# white_noise.net
KiCad netlist of a schematic drawn in Altium Designer
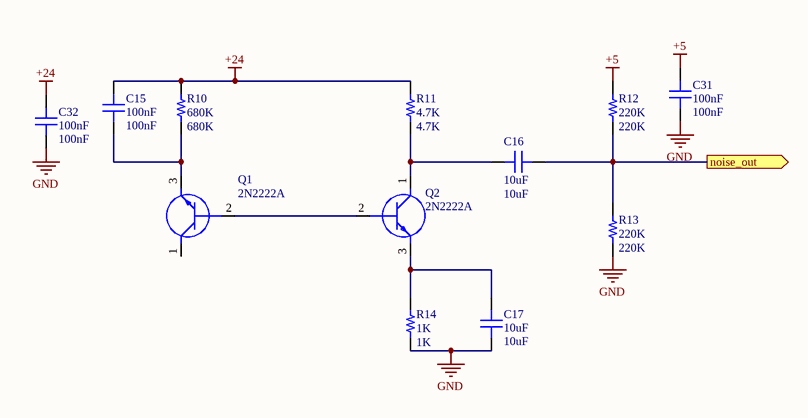
[diagram p0: white_noise.SchDoc]

(export (version "E")
  (design (tool "Eeschema 10.0.6"))
  (components
    (comp (ref "C15")
      (value "100nF")
      (footprint "cap805")
      (description "CAP SMD 0805")
      (fields (field (name "PART NUMBER") "C0805X106K9RAC7800") (field (name "ALTIUM_VALUE") "100nF"))
      (libsource (lib "lamp control-ver2") (part "Capacitor"))
    )
    (comp (ref "C16")
      (value "10uF")
      (footprint "cap805")
      (description "CAP SMD 0805")
      (fields (field (name "PART NUMBER") "C0805X106K9RAC7800") (field (name "ALTIUM_VALUE") "10uF"))
      (libsource (lib "lamp control-ver2") (part "Capacitor"))
    )
    (comp (ref "C17")
      (value "10uF")
      (footprint "cap805")
      (description "CAP SMD 0805")
      (fields (field (name "PART NUMBER") "C0805X106K9RAC7800") (field (name "ALTIUM_VALUE") "10uF"))
      (libsource (lib "lamp control-ver2") (part "Capacitor"))
    )
    (comp (ref "C31")
      (value "100nF")
      (footprint "cap805")
      (description "CAP SMD 0805")
      (fields (field (name "PART NUMBER") "C0805X106K9RAC7800") (field (name "ALTIUM_VALUE") "100nF"))
      (libsource (lib "lamp control-ver2") (part "Capacitor"))
    )
    (comp (ref "C32")
      (value "100nF")
      (footprint "cap805")
      (description "CAP SMD 0805")
      (fields (field (name "PART NUMBER") "C0805X106K9RAC7800") (field (name "ALTIUM_VALUE") "100nF"))
      (libsource (lib "lamp control-ver2") (part "Capacitor"))
    )
    (comp (ref "Q1")
      (value "2N2222A")
      (footprint "soT95p280x130-3n")
      (description "Transistor BJT NPN SMD")
      (libsource (lib "*") (part "2N2222A"))
    )
    (comp (ref "Q2")
      (value "2N2222A")
      (footprint "soT95p280x130-3n")
      (description "Transistor BJT NPN SMD")
      (libsource (lib "*") (part "2N2222A"))
    )
    (comp (ref "R10")
      (value "680K")
      (footprint "0603R")
      (description "RES SMD 0603")
      (fields (field (name "PART NUMBER") "RCS0805100KFKEA") (field (name "ALTIUM_VALUE") "680K"))
      (libsource (lib "lamp control-ver2") (part "Resistor"))
    )
    (comp (ref "R11")
      (value "4.7K")
      (footprint "0603R")
      (description "RES SMD 0603")
      (fields (field (name "PART NUMBER") "RCS0805100KFKEA") (field (name "ALTIUM_VALUE") "4.7K"))
      (libsource (lib "lamp control-ver2") (part "Resistor"))
    )
    (comp (ref "R12")
      (value "220K")
      (footprint "0603R")
      (description "RES SMD 0603")
      (fields (field (name "PART NUMBER") "RCS0805100KFKEA") (field (name "ALTIUM_VALUE") "220K"))
      (libsource (lib "lamp control-ver2") (part "Resistor"))
    )
    (comp (ref "R13")
      (value "220K")
      (footprint "0603R")
      (description "RES SMD 0603")
      (fields (field (name "PART NUMBER") "RCS0805100KFKEA") (field (name "ALTIUM_VALUE") "220K"))
      (libsource (lib "lamp control-ver2") (part "Resistor"))
    )
    (comp (ref "R14")
      (value "1K")
      (footprint "0603R")
      (description "RES SMD 0603")
      (fields (field (name "PART NUMBER") "RCS0805100KFKEA") (field (name "ALTIUM_VALUE") "1K"))
      (libsource (lib "lamp control-ver2") (part "Resistor"))
    )
  )
  (nets
    (net (code "1") (name "+5") (class "Default")
      (node (ref "C31") (pin "1") (pinfunction "1_1") (pintype "passive"))
      (node (ref "R12") (pin "2") (pinfunction "2_2") (pintype "passive"))
    )
    (net (code "2") (name "+24") (class "Default")
      (node (ref "C15") (pin "2") (pinfunction "2_2") (pintype "passive"))
      (node (ref "C32") (pin "1") (pinfunction "1_1") (pintype "passive"))
      (node (ref "R10") (pin "2") (pinfunction "2_2") (pintype "passive"))
      (node (ref "R11") (pin "2") (pinfunction "2_2") (pintype "passive"))
    )
    (net (code "3") (name "/noise_out") (class "Default")
      (node (ref "C16") (pin "1") (pinfunction "1_1") (pintype "passive"))
      (node (ref "R12") (pin "1") (pinfunction "1_1") (pintype "passive"))
      (node (ref "R13") (pin "2") (pinfunction "2_2") (pintype "passive"))
    )
    (net (code "4") (name "GND") (class "Default")
      (node (ref "C17") (pin "1") (pinfunction "1_1") (pintype "passive"))
      (node (ref "C31") (pin "2") (pinfunction "2_2") (pintype "passive"))
      (node (ref "C32") (pin "2") (pinfunction "2_2") (pintype "passive"))
      (node (ref "R13") (pin "1") (pinfunction "1_1") (pintype "passive"))
      (node (ref "R14") (pin "1") (pinfunction "1_1") (pintype "passive"))
    )
    (net (code "5") (name "Net-(Q1-B)") (class "Default")
      (node (ref "Q1") (pin "2") (pinfunction "B_2") (pintype "passive"))
      (node (ref "Q2") (pin "2") (pinfunction "B_2") (pintype "passive"))
    )
    (net (code "6") (name "Net-(Q1-E)") (class "Default")
      (node (ref "C15") (pin "1") (pinfunction "1_1") (pintype "passive"))
      (node (ref "Q1") (pin "3") (pinfunction "E_3") (pintype "passive"))
      (node (ref "R10") (pin "1") (pinfunction "1_1") (pintype "passive"))
    )
    (net (code "7") (name "Net-(Q2-C)") (class "Default")
      (node (ref "C16") (pin "2") (pinfunction "2_2") (pintype "passive"))
      (node (ref "Q2") (pin "1") (pinfunction "C_1") (pintype "passive"))
      (node (ref "R11") (pin "1") (pinfunction "1_1") (pintype "passive"))
    )
    (net (code "8") (name "Net-(Q2-E)") (class "Default")
      (node (ref "C17") (pin "2") (pinfunction "2_2") (pintype "passive"))
      (node (ref "Q2") (pin "3") (pinfunction "E_3") (pintype "passive"))
      (node (ref "R14") (pin "2") (pinfunction "2_2") (pintype "passive"))
    )
    (net (code "9") (name "unconnected-(Q1-C-Pad1)") (class "Default")
      (node (ref "Q1") (pin "1") (pinfunction "C_1") (pintype "passive"))
    )
  )
)
